# FTDI-UART-I2C.net
KiCad netlist of a schematic drawn in EAGLE
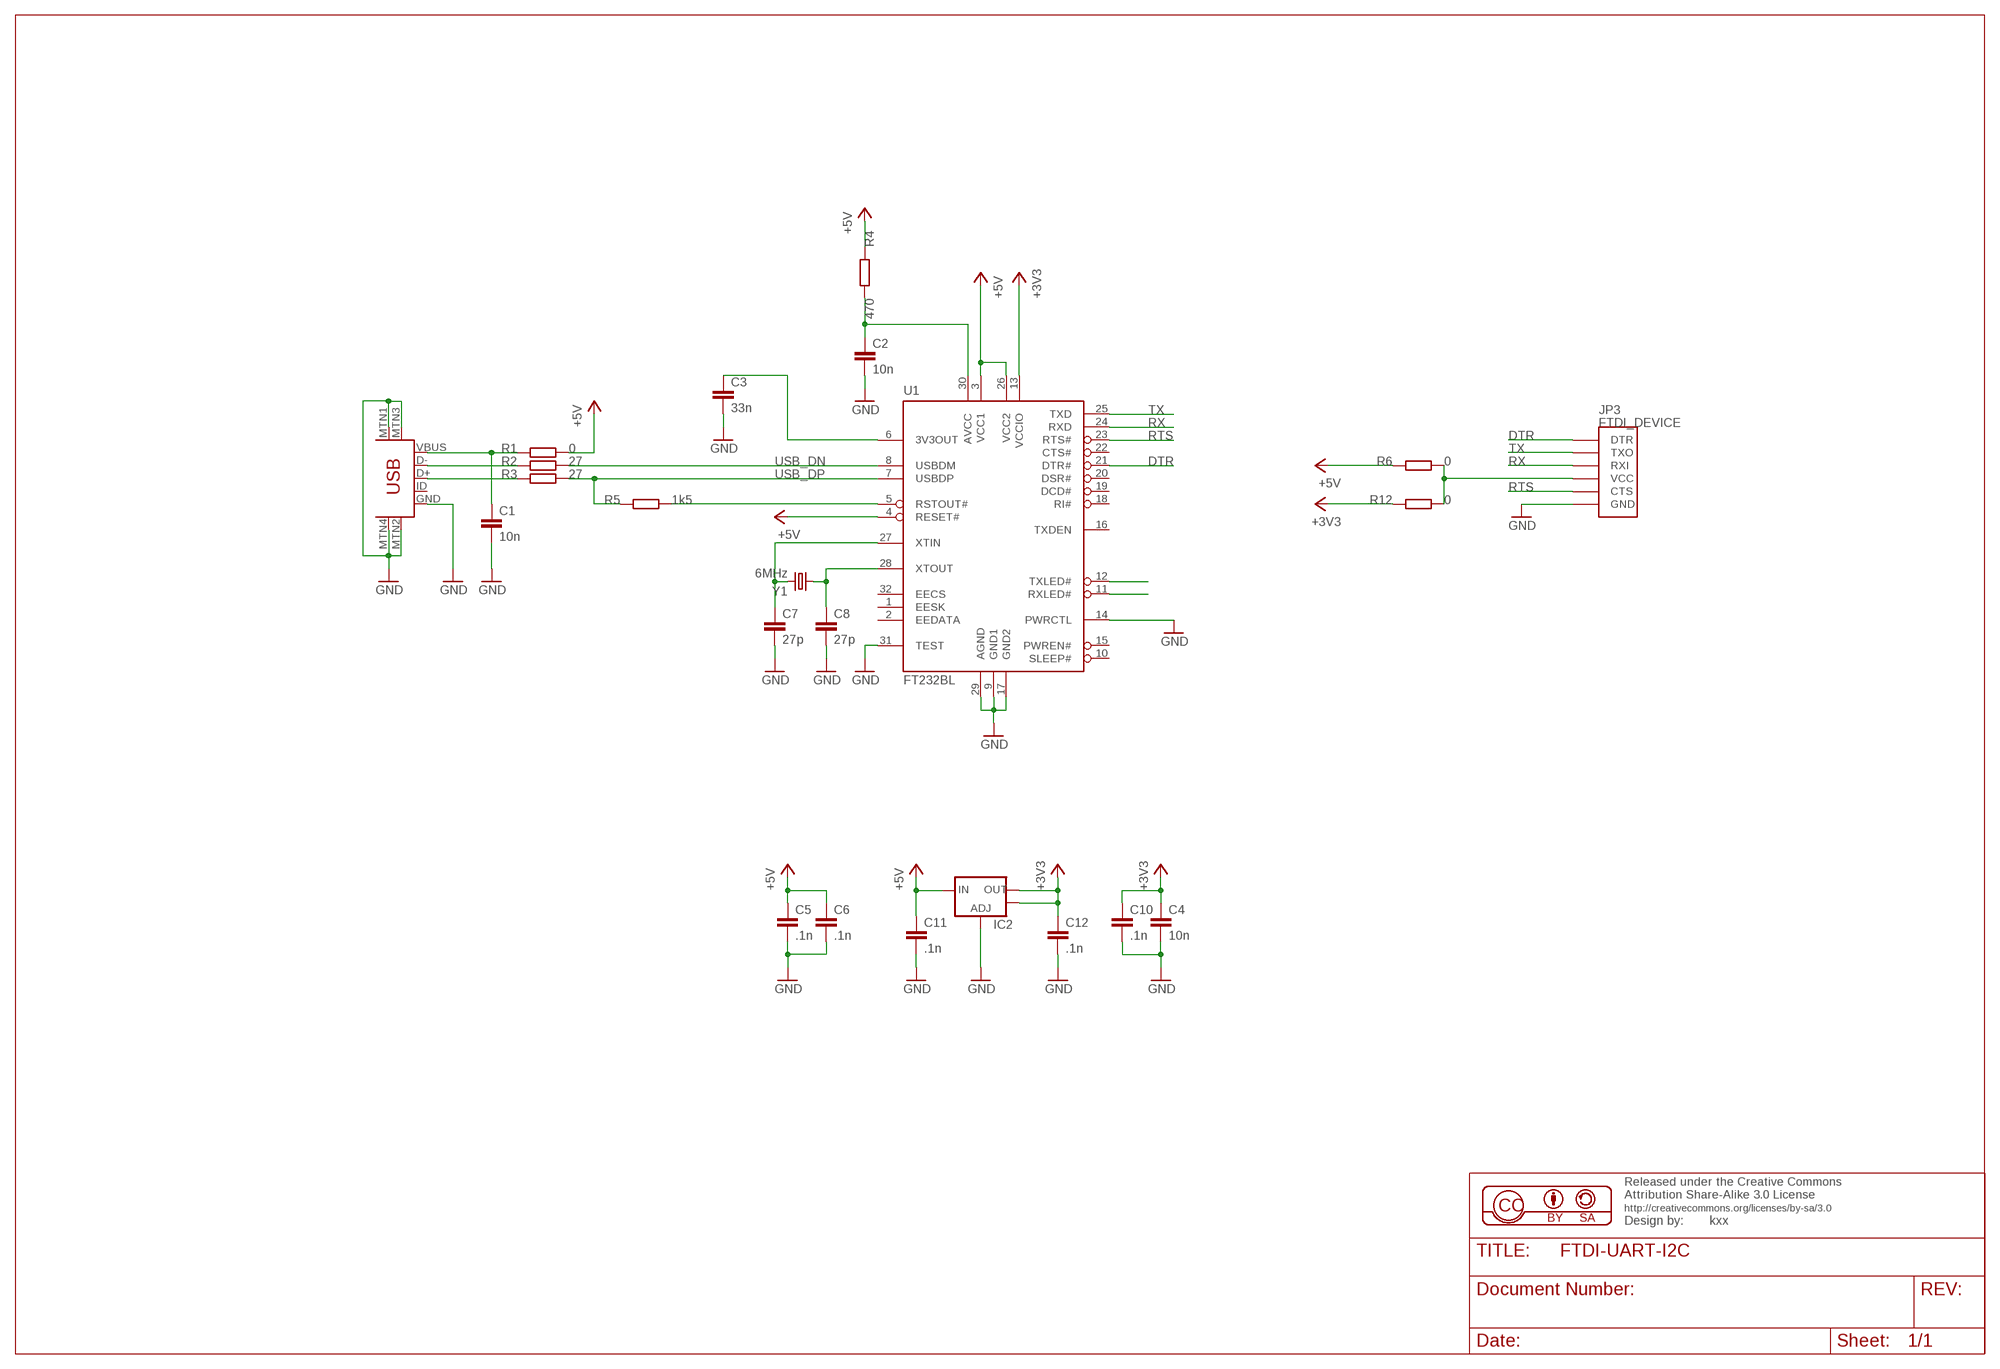
[diagram p0: schematic, sheet 1]

(export (version "E")
  (design (tool "Eeschema 10.0.6"))
  (components
    (comp (ref "C1")
      (value "10n")
      (footprint "eagle-import:C0805")
      (libsource (lib "eagle-import") (part "C-EUC0805"))
    )
    (comp (ref "C2")
      (value "10n")
      (footprint "eagle-import:C0805")
      (libsource (lib "eagle-import") (part "C-EUC0805"))
    )
    (comp (ref "C3")
      (value "33n")
      (footprint "eagle-import:C0805")
      (libsource (lib "eagle-import") (part "C-EUC0805"))
    )
    (comp (ref "C4")
      (value "10n")
      (footprint "eagle-import:C0805")
      (libsource (lib "eagle-import") (part "C-EUC0805"))
    )
    (comp (ref "C5")
      (value ".1n")
      (footprint "eagle-import:C0805")
      (libsource (lib "eagle-import") (part "C-EUC0805"))
    )
    (comp (ref "C6")
      (value ".1n")
      (footprint "eagle-import:C0805")
      (libsource (lib "eagle-import") (part "C-EUC0805"))
    )
    (comp (ref "C7")
      (value "27p")
      (footprint "eagle-import:C0805")
      (libsource (lib "eagle-import") (part "C-EUC0805"))
    )
    (comp (ref "C8")
      (value "27p")
      (footprint "eagle-import:C0805")
      (libsource (lib "eagle-import") (part "C-EUC0805"))
    )
    (comp (ref "C10")
      (value ".1n")
      (footprint "eagle-import:C0805")
      (libsource (lib "eagle-import") (part "C-EUC0805"))
    )
    (comp (ref "C11")
      (value ".1n")
      (footprint "eagle-import:C0805")
      (libsource (lib "eagle-import") (part "C-EUC0805"))
    )
    (comp (ref "C12")
      (value ".1n")
      (footprint "eagle-import:C0805")
      (libsource (lib "eagle-import") (part "C-EUC0805"))
    )
    (comp (ref "IC2")
      (value "V_REG_LM1117SOT223")
      (footprint "eagle-import:SOT223")
      (libsource (lib "eagle-import") (part "V_REG_LM1117SOT223"))
    )
    (comp (ref "JP3")
      (value "FTDI_DEVICE")
      (footprint "eagle-import:FTDI_DEVICE_SIDE")
      (libsource (lib "eagle-import") (part "FTDI_DEVICE"))
    )
    (comp (ref "R1")
      (value "0")
      (footprint "eagle-import:R0603")
      (libsource (lib "eagle-import") (part "R-EU_R0603"))
    )
    (comp (ref "R2")
      (value "27")
      (footprint "eagle-import:R0603")
      (libsource (lib "eagle-import") (part "R-EU_R0603"))
    )
    (comp (ref "R3")
      (value "27")
      (footprint "eagle-import:R0603")
      (libsource (lib "eagle-import") (part "R-EU_R0603"))
    )
    (comp (ref "R4")
      (value "470")
      (footprint "eagle-import:R0603")
      (libsource (lib "eagle-import") (part "R-EU_R0603"))
    )
    (comp (ref "R5")
      (value "1k5")
      (footprint "eagle-import:R0603")
      (libsource (lib "eagle-import") (part "R-EU_R0603"))
    )
    (comp (ref "R6")
      (value "0")
      (footprint "eagle-import:R0603")
      (libsource (lib "eagle-import") (part "R-EU_R0603"))
    )
    (comp (ref "R12")
      (value "0")
      (footprint "eagle-import:R0603")
      (libsource (lib "eagle-import") (part "R-EU_R0603"))
    )
    (comp (ref "U$2")
      (value "USB-MINIB-5PIN")
      (footprint "eagle-import:USB-MINIB")
      (libsource (lib "eagle-import") (part "USB-MINIB-5PIN"))
    )
    (comp (ref "U1")
      (value "FT232BL")
      (footprint "eagle-import:LQFP32")
      (libsource (lib "eagle-import") (part "FT232BL"))
    )
    (comp (ref "Y1")
      (value "6MHz")
      (footprint "eagle-import:HC49U-V")
      (libsource (lib "eagle-import") (part "CRYSTALHC49UV"))
    )
  )
  (nets
    (net (code "1") (name "+3V3") (class "Default")
      (node (ref "C10") (pin "1") (pinfunction "1_1") (pintype "passive"))
      (node (ref "C12") (pin "1") (pinfunction "1_1") (pintype "passive"))
      (node (ref "C4") (pin "1") (pinfunction "1_1") (pintype "passive"))
      (node (ref "IC2") (pin "2") (pinfunction "OUT_2") (pintype "output"))
      (node (ref "IC2") (pin "4") (pinfunction "OUT_4") (pintype "output"))
      (node (ref "R12") (pin "1") (pinfunction "1_1") (pintype "passive"))
      (node (ref "U1") (pin "13") (pinfunction "VCCIO_13") (pintype "power_in"))
    )
    (net (code "2") (name "+5V") (class "Default")
      (node (ref "C11") (pin "1") (pinfunction "1_1") (pintype "passive"))
      (node (ref "C5") (pin "1") (pinfunction "1_1") (pintype "passive"))
      (node (ref "C6") (pin "1") (pinfunction "1_1") (pintype "passive"))
      (node (ref "IC2") (pin "3") (pinfunction "IN_3") (pintype "input"))
      (node (ref "R1") (pin "2") (pinfunction "2_2") (pintype "passive"))
      (node (ref "R4") (pin "1") (pinfunction "1_1") (pintype "passive"))
      (node (ref "R6") (pin "1") (pinfunction "1_1") (pintype "passive"))
      (node (ref "U1") (pin "26") (pinfunction "VCC2_26") (pintype "power_in"))
      (node (ref "U1") (pin "3") (pinfunction "VCC1_3") (pintype "power_in"))
      (node (ref "U1") (pin "4") (pinfunction "RESET#_4") (pintype "input"))
    )
    (net (code "3") (name "/DTR") (class "Default")
      (node (ref "JP3") (pin "P$1") (pinfunction "DTR_P$1") (pintype "bidirectional"))
      (node (ref "U1") (pin "21") (pinfunction "DTR#_21") (pintype "output"))
    )
    (net (code "4") (name "/RTS") (class "Default")
      (node (ref "JP3") (pin "P$5") (pinfunction "CTS_P$5") (pintype "bidirectional"))
      (node (ref "U1") (pin "23") (pinfunction "RTS#_23") (pintype "output"))
    )
    (net (code "5") (name "/RX") (class "Default")
      (node (ref "JP3") (pin "P$3") (pinfunction "RXI_P$3") (pintype "bidirectional"))
      (node (ref "U1") (pin "24") (pinfunction "RXD_24") (pintype "input"))
    )
    (net (code "6") (name "/TX") (class "Default")
      (node (ref "JP3") (pin "P$2") (pinfunction "TXO_P$2") (pintype "bidirectional"))
      (node (ref "U1") (pin "25") (pinfunction "TXD_25") (pintype "output"))
    )
    (net (code "7") (name "/USB_DN") (class "Default")
      (node (ref "R2") (pin "2") (pinfunction "2_2") (pintype "passive"))
      (node (ref "U1") (pin "8") (pinfunction "USBDM_8") (pintype "bidirectional"))
    )
    (net (code "8") (name "/USB_DP") (class "Default")
      (node (ref "R3") (pin "2") (pinfunction "2_2") (pintype "passive"))
      (node (ref "R5") (pin "1") (pinfunction "1_1") (pintype "passive"))
      (node (ref "U1") (pin "7") (pinfunction "USBDP_7") (pintype "bidirectional"))
    )
    (net (code "9") (name "GND") (class "Default")
      (node (ref "C1") (pin "2") (pinfunction "2_2") (pintype "passive"))
      (node (ref "C10") (pin "2") (pinfunction "2_2") (pintype "passive"))
      (node (ref "C11") (pin "2") (pinfunction "2_2") (pintype "passive"))
      (node (ref "C12") (pin "2") (pinfunction "2_2") (pintype "passive"))
      (node (ref "C2") (pin "2") (pinfunction "2_2") (pintype "passive"))
      (node (ref "C3") (pin "2") (pinfunction "2_2") (pintype "passive"))
      (node (ref "C4") (pin "2") (pinfunction "2_2") (pintype "passive"))
      (node (ref "C5") (pin "2") (pinfunction "2_2") (pintype "passive"))
      (node (ref "C6") (pin "2") (pinfunction "2_2") (pintype "passive"))
      (node (ref "C7") (pin "2") (pinfunction "2_2") (pintype "passive"))
      (node (ref "C8") (pin "2") (pinfunction "2_2") (pintype "passive"))
      (node (ref "IC2") (pin "1") (pinfunction "ADJ_1") (pintype "input"))
      (node (ref "JP3") (pin "P$6") (pinfunction "GND_P$6") (pintype "bidirectional"))
      (node (ref "U$2") (pin "GND") (pinfunction "GND_GND") (pintype "bidirectional"))
      (node (ref "U$2") (pin "MTN1") (pinfunction "MTN2_MTN1") (pintype "bidirectional"))
      (node (ref "U$2") (pin "MTN2") (pinfunction "MTN3_MTN2") (pintype "bidirectional"))
      (node (ref "U$2") (pin "MTN3") (pinfunction "MTN1_MTN3") (pintype "bidirectional"))
      (node (ref "U$2") (pin "MTN4") (pinfunction "MTN4_MTN4") (pintype "bidirectional"))
      (node (ref "U1") (pin "14") (pinfunction "PWRCTL_14") (pintype "input"))
      (node (ref "U1") (pin "17") (pinfunction "GND2_17") (pintype "power_in"))
      (node (ref "U1") (pin "29") (pinfunction "AGND_29") (pintype "power_in"))
      (node (ref "U1") (pin "31") (pinfunction "TEST_31") (pintype "input"))
      (node (ref "U1") (pin "9") (pinfunction "GND1_9") (pintype "power_in"))
    )
    (net (code "10") (name "Net-(C1-Pad1)") (class "Default")
      (node (ref "C1") (pin "1") (pinfunction "1_1") (pintype "passive"))
      (node (ref "R1") (pin "1") (pinfunction "1_1") (pintype "passive"))
      (node (ref "U$2") (pin "VBUS") (pinfunction "VBUS_VBUS") (pintype "bidirectional"))
    )
    (net (code "11") (name "Net-(JP3-VCC)") (class "Default")
      (node (ref "JP3") (pin "P$4") (pinfunction "VCC_P$4") (pintype "bidirectional"))
      (node (ref "R12") (pin "2") (pinfunction "2_2") (pintype "passive"))
      (node (ref "R6") (pin "2") (pinfunction "2_2") (pintype "passive"))
    )
    (net (code "12") (name "Net-(R2-Pad1)") (class "Default")
      (node (ref "R2") (pin "1") (pinfunction "1_1") (pintype "passive"))
      (node (ref "U$2") (pin "D-") (pinfunction "D-_D-") (pintype "bidirectional"))
    )
    (net (code "13") (name "Net-(R3-Pad1)") (class "Default")
      (node (ref "R3") (pin "1") (pinfunction "1_1") (pintype "passive"))
      (node (ref "U$2") (pin "D+") (pinfunction "D+_D+") (pintype "bidirectional"))
    )
    (net (code "14") (name "Net-(U1-3V3OUT)") (class "Default")
      (node (ref "C3") (pin "1") (pinfunction "1_1") (pintype "passive"))
      (node (ref "U1") (pin "6") (pinfunction "3V3OUT_6") (pintype "output"))
    )
    (net (code "15") (name "Net-(U1-AVCC)") (class "Default")
      (node (ref "C2") (pin "1") (pinfunction "1_1") (pintype "passive"))
      (node (ref "R4") (pin "2") (pinfunction "2_2") (pintype "passive"))
      (node (ref "U1") (pin "30") (pinfunction "AVCC_30") (pintype "power_in"))
    )
    (net (code "16") (name "Net-(U1-RSTOUT#)") (class "Default")
      (node (ref "R5") (pin "2") (pinfunction "2_2") (pintype "passive"))
      (node (ref "U1") (pin "5") (pinfunction "RSTOUT#_5") (pintype "output"))
    )
    (net (code "17") (name "Net-(U1-XTIN)") (class "Default")
      (node (ref "C7") (pin "1") (pinfunction "1_1") (pintype "passive"))
      (node (ref "U1") (pin "27") (pinfunction "XTIN_27") (pintype "input"))
      (node (ref "Y1") (pin "2") (pinfunction "2_2") (pintype "passive"))
    )
    (net (code "18") (name "Net-(U1-XTOUT)") (class "Default")
      (node (ref "C8") (pin "1") (pinfunction "1_1") (pintype "passive"))
      (node (ref "U1") (pin "28") (pinfunction "XTOUT_28") (pintype "output"))
      (node (ref "Y1") (pin "1") (pinfunction "1_1") (pintype "passive"))
    )
    (net (code "19") (name "unconnected-(U$2-PadID)") (class "Default")
      (node (ref "U$2") (pin "ID") (pinfunction "ID_ID") (pintype "bidirectional"))
    )
    (net (code "20") (name "unconnected-(U1-CTS#-Pad22)") (class "Default")
      (node (ref "U1") (pin "22") (pinfunction "CTS#_22") (pintype "input"))
    )
    (net (code "21") (name "unconnected-(U1-DCD#-Pad19)") (class "Default")
      (node (ref "U1") (pin "19") (pinfunction "DCD#_19") (pintype "input"))
    )
    (net (code "22") (name "unconnected-(U1-DSR#-Pad20)") (class "Default")
      (node (ref "U1") (pin "20") (pinfunction "DSR#_20") (pintype "input"))
    )
    (net (code "23") (name "unconnected-(U1-EECS-Pad32)") (class "Default")
      (node (ref "U1") (pin "32") (pinfunction "EECS_32") (pintype "bidirectional"))
    )
    (net (code "24") (name "unconnected-(U1-EEDATA-Pad2)") (class "Default")
      (node (ref "U1") (pin "2") (pinfunction "EEDATA_2") (pintype "bidirectional"))
    )
    (net (code "25") (name "unconnected-(U1-EESK-Pad1)") (class "Default")
      (node (ref "U1") (pin "1") (pinfunction "EESK_1") (pintype "output"))
    )
    (net (code "26") (name "unconnected-(U1-PWREN#-Pad15)") (class "Default")
      (node (ref "U1") (pin "15") (pinfunction "PWREN#_15") (pintype "output"))
    )
    (net (code "27") (name "unconnected-(U1-RI#-Pad18)") (class "Default")
      (node (ref "U1") (pin "18") (pinfunction "RI#_18") (pintype "input"))
    )
    (net (code "28") (name "unconnected-(U1-RXLED#-Pad11)") (class "Default")
      (node (ref "U1") (pin "11") (pinfunction "RXLED#_11") (pintype "open_collector"))
    )
    (net (code "29") (name "unconnected-(U1-SLEEP#-Pad10)") (class "Default")
      (node (ref "U1") (pin "10") (pinfunction "SLEEP#_10") (pintype "output"))
    )
    (net (code "30") (name "unconnected-(U1-TXDEN-Pad16)") (class "Default")
      (node (ref "U1") (pin "16") (pinfunction "TXDEN_16") (pintype "output"))
    )
    (net (code "31") (name "unconnected-(U1-TXLED#-Pad12)") (class "Default")
      (node (ref "U1") (pin "12") (pinfunction "TXLED#_12") (pintype "open_collector"))
    )
  )
)
